# pthbadge_batt6.net
KiCad netlist of a schematic drawn in EAGLE
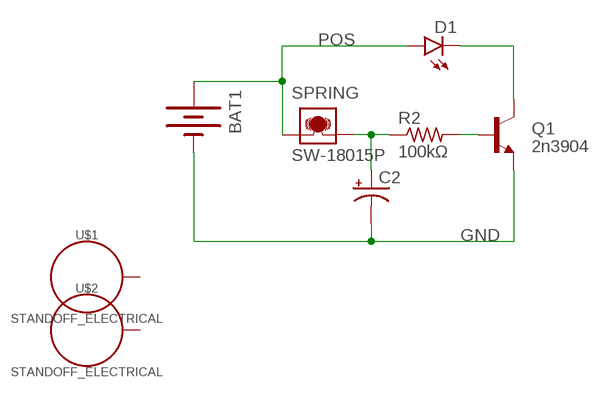
[diagram p0: schematic, sheet 1]

(export (version "E")
  (design (tool "Eeschema 10.0.6"))
  (components
    (comp (ref "BAT1")
      (value "BATTERY20PTH")
      (footprint "eagle-import:BATTCOM_20MM_PTH")
      (libsource (lib "eagle-import") (part "BATTERY20PTH"))
    )
    (comp (ref "C2")
      (value "CPOL-USE2-4")
      (footprint "eagle-import:E2-4")
      (libsource (lib "eagle-import") (part "CPOL-USE2-4"))
    )
    (comp (ref "D1")
      (value "LED5MM")
      (footprint "eagle-import:LED5MM")
      (libsource (lib "eagle-import") (part "LED5MM"))
    )
    (comp (ref "Q1")
      (value "2n3904")
      (footprint "eagle-import:TO-92")
      (libsource (lib "eagle-import") (part "TRANSISTOR_NPN2N3904"))
    )
    (comp (ref "R2")
      (value "100kΩ")
      (footprint "eagle-import:0207_10")
      (libsource (lib "eagle-import") (part "R-US_0207/10"))
    )
    (comp (ref "SPRING")
      (value "SW-18015P")
      (footprint "eagle-import:SW-18015P")
      (fields (field (name "MF") "FARNELL") (field (name "MPN") "CM4400-1."))
      (libsource (lib "eagle-import") (part "SW-18015P"))
    )
    (comp (ref "U$1")
      (value "STANDOFF_ELECTRICAL")
      (footprint "eagle-import:STANDOFF-ELECTRICAL")
      (libsource (lib "eagle-import") (part "STANDOFF_ELECTRICAL"))
    )
    (comp (ref "U$2")
      (value "STANDOFF_ELECTRICAL")
      (footprint "eagle-import:STANDOFF-ELECTRICAL")
      (libsource (lib "eagle-import") (part "STANDOFF_ELECTRICAL"))
    )
  )
  (nets
    (net (code "1") (name "/GND") (class "Default")
      (node (ref "BAT1") (pin "2") (pinfunction "-_2") (pintype "power_in"))
      (node (ref "C2") (pin "-") (pinfunction "-_-") (pintype "passive"))
      (node (ref "Q1") (pin "1") (pinfunction "E_1") (pintype "passive"))
    )
    (net (code "2") (name "/POS") (class "Default")
      (node (ref "BAT1") (pin "1") (pinfunction "+_1") (pintype "power_in"))
      (node (ref "D1") (pin "A") (pinfunction "A_A") (pintype "passive"))
      (node (ref "SPRING") (pin "1") (pinfunction "1_1") (pintype "passive"))
    )
    (net (code "3") (name "Net-(C2-Pad+)") (class "Default")
      (node (ref "C2") (pin "+") (pinfunction "+_+") (pintype "passive"))
      (node (ref "R2") (pin "1") (pinfunction "1_1") (pintype "passive"))
      (node (ref "SPRING") (pin "2") (pinfunction "2_2") (pintype "passive"))
    )
    (net (code "4") (name "Net-(D1-C)") (class "Default")
      (node (ref "D1") (pin "K") (pinfunction "C_K") (pintype "passive"))
      (node (ref "Q1") (pin "3") (pinfunction "C_3") (pintype "passive"))
    )
    (net (code "5") (name "Net-(Q1-B)") (class "Default")
      (node (ref "Q1") (pin "2") (pinfunction "B_2") (pintype "passive"))
      (node (ref "R2") (pin "2") (pinfunction "2_2") (pintype "passive"))
    )
    (net (code "6") (name "unconnected-(U$1-P$1-PadP1)") (class "Default")
      (node (ref "U$1") (pin "P1") (pinfunction "P$1_P1") (pintype "bidirectional"))
    )
    (net (code "7") (name "unconnected-(U$2-P$1-PadP1)") (class "Default")
      (node (ref "U$2") (pin "P1") (pinfunction "P$1_P1") (pintype "bidirectional"))
    )
  )
)
